# can-hat.net
KiCad netlist of a schematic drawn in EAGLE
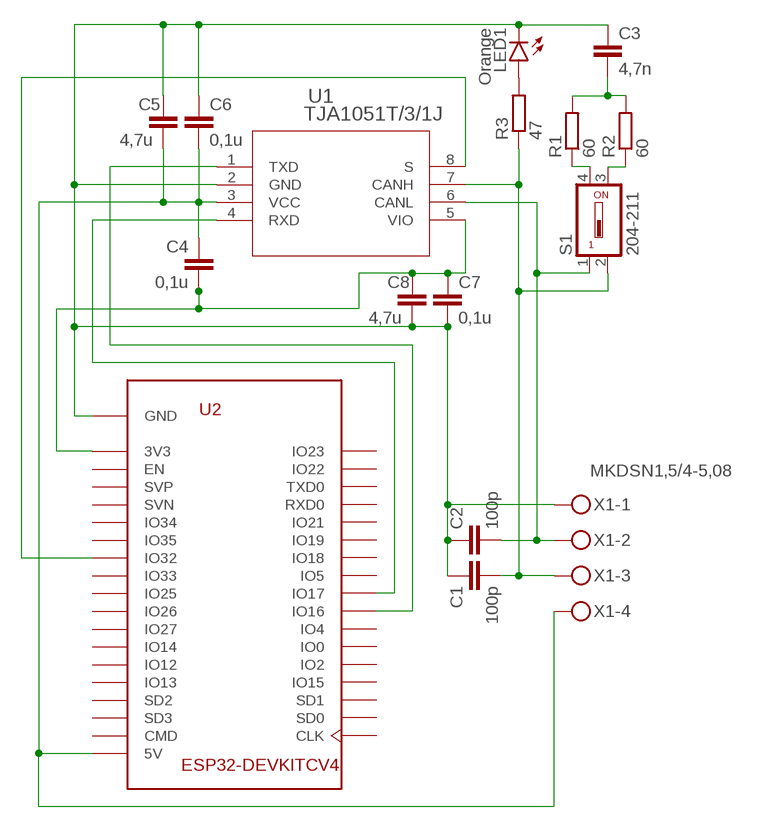
[diagram p0: schematic, sheet 1]

(export (version "E")
  (design (tool "Eeschema 10.0.6"))
  (components
    (comp (ref "C1")
      (value "100p")
      (footprint "eagle-import:C0603")
      (libsource (lib "eagle-import") (part "C-EUC0603"))
    )
    (comp (ref "C2")
      (value "100p")
      (footprint "eagle-import:C0603")
      (libsource (lib "eagle-import") (part "C-EUC0603"))
    )
    (comp (ref "C3")
      (value "4,7n")
      (footprint "eagle-import:C0603")
      (libsource (lib "eagle-import") (part "C-EUC0603"))
    )
    (comp (ref "C4")
      (value "0,1u")
      (footprint "eagle-import:C0603")
      (libsource (lib "eagle-import") (part "C-EUC0603"))
    )
    (comp (ref "C5")
      (value "4,7u")
      (footprint "eagle-import:C0603")
      (libsource (lib "eagle-import") (part "C-EUC0603"))
    )
    (comp (ref "C6")
      (value "0,1u")
      (footprint "eagle-import:C0603")
      (libsource (lib "eagle-import") (part "C-EUC0603"))
    )
    (comp (ref "C7")
      (value "0,1u")
      (footprint "eagle-import:C0603")
      (libsource (lib "eagle-import") (part "C-EUC0603"))
    )
    (comp (ref "C8")
      (value "4,7u")
      (footprint "eagle-import:C0603")
      (libsource (lib "eagle-import") (part "C-EUC0603"))
    )
    (comp (ref "LED1")
      (value "Orange")
      (footprint "eagle-import:CHIP-LED0603")
      (libsource (lib "eagle-import") (part "LEDCHIP-LED0603"))
    )
    (comp (ref "R1")
      (value "60")
      (footprint "eagle-import:R0603")
      (libsource (lib "eagle-import") (part "R-EU_R0603"))
    )
    (comp (ref "R2")
      (value "60")
      (footprint "eagle-import:R0603")
      (libsource (lib "eagle-import") (part "R-EU_R0603"))
    )
    (comp (ref "R3")
      (value "47")
      (footprint "eagle-import:R0603")
      (libsource (lib "eagle-import") (part "R-EU_R0603"))
    )
    (comp (ref "S1")
      (value "204-211")
      (footprint "eagle-import:204-211ST")
      (libsource (lib "eagle-import") (part "204-211"))
    )
    (comp (ref "U1")
      (value "TJA1051T/3/1J")
      (footprint "eagle-import:SO8_SOT96-1_NXP")
      (fields (field (name "COPYRIGHT") "Copyright (C) 2018 Accelerated Designs. All rights reserved"))
      (libsource (lib "eagle-import") (part "TJA1051T/3/1J"))
    )
    (comp (ref "U2")
      (value "ESP32-DEVKITCV4")
      (footprint "eagle-import:DEVKIT-C")
      (libsource (lib "eagle-import") (part "ESP32-DEVKITCV4"))
    )
    (comp (ref "X1")
      (value "MKDSN1,5/4-5,08")
      (footprint "eagle-import:MKDSN1,5_4-5,08")
      (libsource (lib "eagle-import") (part "MKDSN1,5/4-5,08"))
    )
  )
  (nets
    (net (code "1") (name "Net-(C3-Pad2)") (class "Default")
      (node (ref "C3") (pin "2") (pinfunction "2_2") (pintype "passive"))
      (node (ref "R1") (pin "2") (pinfunction "2_2") (pintype "passive"))
      (node (ref "R2") (pin "2") (pinfunction "2_2") (pintype "passive"))
    )
    (net (code "2") (name "Net-(LED1-PadA)") (class "Default")
      (node (ref "LED1") (pin "A") (pinfunction "A_A") (pintype "passive"))
      (node (ref "R3") (pin "2") (pinfunction "2_2") (pintype "passive"))
    )
    (net (code "3") (name "Net-(R1-Pad1)") (class "Default")
      (node (ref "R1") (pin "1") (pinfunction "1_1") (pintype "passive"))
      (node (ref "S1") (pin "4") (pinfunction "4_4") (pintype "passive"))
    )
    (net (code "4") (name "Net-(R2-Pad1)") (class "Default")
      (node (ref "R2") (pin "1") (pinfunction "1_1") (pintype "passive"))
      (node (ref "S1") (pin "3") (pinfunction "3_3") (pintype "passive"))
    )
    (net (code "5") (name "Net-(U1-CANH)") (class "Default")
      (node (ref "C1") (pin "1") (pinfunction "1_1") (pintype "passive"))
      (node (ref "R3") (pin "1") (pinfunction "1_1") (pintype "passive"))
      (node (ref "S1") (pin "2") (pinfunction "2_2") (pintype "passive"))
      (node (ref "U1") (pin "7") (pinfunction "CANH_7") (pintype "bidirectional"))
      (node (ref "X1") (pin "3") (pinfunction "KL_3") (pintype "passive"))
    )
    (net (code "6") (name "Net-(U1-CANL)") (class "Default")
      (node (ref "C2") (pin "2") (pinfunction "2_2") (pintype "passive"))
      (node (ref "S1") (pin "1") (pinfunction "1_1") (pintype "passive"))
      (node (ref "U1") (pin "6") (pinfunction "CANL_6") (pintype "bidirectional"))
      (node (ref "X1") (pin "2") (pinfunction "KL_2") (pintype "passive"))
    )
    (net (code "7") (name "Net-(U1-GND)") (class "Default")
      (node (ref "C1") (pin "2") (pinfunction "2_2") (pintype "passive"))
      (node (ref "C2") (pin "1") (pinfunction "1_1") (pintype "passive"))
      (node (ref "C3") (pin "1") (pinfunction "1_1") (pintype "passive"))
      (node (ref "C5") (pin "1") (pinfunction "1_1") (pintype "passive"))
      (node (ref "C6") (pin "1") (pinfunction "1_1") (pintype "passive"))
      (node (ref "C7") (pin "2") (pinfunction "2_2") (pintype "passive"))
      (node (ref "C8") (pin "2") (pinfunction "2_2") (pintype "passive"))
      (node (ref "LED1") (pin "C") (pinfunction "C_C") (pintype "passive"))
      (node (ref "U1") (pin "2") (pinfunction "GND_2") (pintype "passive"))
      (node (ref "U2") (pin "GND1") (pinfunction "GND_GND1") (pintype "power_in"))
      (node (ref "U2") (pin "GND2") (pinfunction "GND_GND2") (pintype "power_in"))
      (node (ref "U2") (pin "GND3") (pinfunction "GND_GND3") (pintype "power_in"))
      (node (ref "X1") (pin "1") (pinfunction "KL_1") (pintype "passive"))
    )
    (net (code "8") (name "Net-(U1-RXD)") (class "Default")
      (node (ref "U1") (pin "4") (pinfunction "RXD_4") (pintype "output"))
      (node (ref "U2") (pin "IO17") (pinfunction "IO17_IO17") (pintype "bidirectional"))
    )
    (net (code "9") (name "Net-(U1-S)") (class "Default")
      (node (ref "U1") (pin "8") (pinfunction "S_8") (pintype "input"))
      (node (ref "U2") (pin "IO32") (pinfunction "IO32_IO32") (pintype "bidirectional"))
    )
    (net (code "10") (name "Net-(U1-TXD)") (class "Default")
      (node (ref "U1") (pin "1") (pinfunction "TXD_1") (pintype "input"))
      (node (ref "U2") (pin "IO16") (pinfunction "IO16_IO16") (pintype "bidirectional"))
    )
    (net (code "11") (name "Net-(U1-VCC)") (class "Default")
      (node (ref "C4") (pin "1") (pinfunction "1_1") (pintype "passive"))
      (node (ref "C5") (pin "2") (pinfunction "2_2") (pintype "passive"))
      (node (ref "C6") (pin "2") (pinfunction "2_2") (pintype "passive"))
      (node (ref "U1") (pin "3") (pinfunction "VCC_3") (pintype "power_in"))
      (node (ref "U2") (pin "5V") (pinfunction "5V_5V") (pintype "power_in"))
      (node (ref "X1") (pin "4") (pinfunction "KL_4") (pintype "passive"))
    )
    (net (code "12") (name "Net-(U1-VIO)") (class "Default")
      (node (ref "C4") (pin "2") (pinfunction "2_2") (pintype "passive"))
      (node (ref "C7") (pin "1") (pinfunction "1_1") (pintype "passive"))
      (node (ref "C8") (pin "1") (pinfunction "1_1") (pintype "passive"))
      (node (ref "U1") (pin "5") (pinfunction "VIO_5") (pintype "power_in"))
      (node (ref "U2") (pin "3V3") (pinfunction "3V3_3V3") (pintype "power_in"))
    )
    (net (code "13") (name "unconnected-(U2-PadCLK)") (class "Default")
      (node (ref "U2") (pin "CLK") (pinfunction "CLK_CLK") (pintype "bidirectional"))
    )
    (net (code "14") (name "unconnected-(U2-PadCMD)") (class "Default")
      (node (ref "U2") (pin "CMD") (pinfunction "CMD_CMD") (pintype "bidirectional"))
    )
    (net (code "15") (name "unconnected-(U2-PadEN)") (class "Default")
      (node (ref "U2") (pin "EN") (pinfunction "EN_EN") (pintype "bidirectional"))
    )
    (net (code "16") (name "unconnected-(U2-PadIO0)") (class "Default")
      (node (ref "U2") (pin "IO0") (pinfunction "IO0_IO0") (pintype "bidirectional"))
    )
    (net (code "17") (name "unconnected-(U2-PadIO2)") (class "Default")
      (node (ref "U2") (pin "IO2") (pinfunction "IO2_IO2") (pintype "bidirectional"))
    )
    (net (code "18") (name "unconnected-(U2-PadIO4)") (class "Default")
      (node (ref "U2") (pin "IO4") (pinfunction "IO4_IO4") (pintype "bidirectional"))
    )
    (net (code "19") (name "unconnected-(U2-PadIO5)") (class "Default")
      (node (ref "U2") (pin "IO5") (pinfunction "IO5_IO5") (pintype "bidirectional"))
    )
    (net (code "20") (name "unconnected-(U2-PadIO12)") (class "Default")
      (node (ref "U2") (pin "IO12") (pinfunction "IO12_IO12") (pintype "bidirectional"))
    )
    (net (code "21") (name "unconnected-(U2-PadIO13)") (class "Default")
      (node (ref "U2") (pin "IO13") (pinfunction "IO13_IO13") (pintype "bidirectional"))
    )
    (net (code "22") (name "unconnected-(U2-PadIO14)") (class "Default")
      (node (ref "U2") (pin "IO14") (pinfunction "IO14_IO14") (pintype "bidirectional"))
    )
    (net (code "23") (name "unconnected-(U2-PadIO15)") (class "Default")
      (node (ref "U2") (pin "IO15") (pinfunction "IO15_IO15") (pintype "bidirectional"))
    )
    (net (code "24") (name "unconnected-(U2-PadIO18)") (class "Default")
      (node (ref "U2") (pin "IO18") (pinfunction "IO18_IO18") (pintype "bidirectional"))
    )
    (net (code "25") (name "unconnected-(U2-PadIO19)") (class "Default")
      (node (ref "U2") (pin "IO19") (pinfunction "IO19_IO19") (pintype "bidirectional"))
    )
    (net (code "26") (name "unconnected-(U2-PadIO21)") (class "Default")
      (node (ref "U2") (pin "IO21") (pinfunction "IO21_IO21") (pintype "bidirectional"))
    )
    (net (code "27") (name "unconnected-(U2-PadIO22)") (class "Default")
      (node (ref "U2") (pin "IO22") (pinfunction "IO22_IO22") (pintype "bidirectional"))
    )
    (net (code "28") (name "unconnected-(U2-PadIO23)") (class "Default")
      (node (ref "U2") (pin "IO23") (pinfunction "IO23_IO23") (pintype "bidirectional"))
    )
    (net (code "29") (name "unconnected-(U2-PadIO25)") (class "Default")
      (node (ref "U2") (pin "IO25") (pinfunction "IO25_IO25") (pintype "bidirectional"))
    )
    (net (code "30") (name "unconnected-(U2-PadIO26)") (class "Default")
      (node (ref "U2") (pin "IO26") (pinfunction "IO26_IO26") (pintype "bidirectional"))
    )
    (net (code "31") (name "unconnected-(U2-PadIO27)") (class "Default")
      (node (ref "U2") (pin "IO27") (pinfunction "IO27_IO27") (pintype "bidirectional"))
    )
    (net (code "32") (name "unconnected-(U2-PadIO33)") (class "Default")
      (node (ref "U2") (pin "IO33") (pinfunction "IO33_IO33") (pintype "bidirectional"))
    )
    (net (code "33") (name "unconnected-(U2-PadIO34)") (class "Default")
      (node (ref "U2") (pin "IO34") (pinfunction "IO34_IO34") (pintype "bidirectional"))
    )
    (net (code "34") (name "unconnected-(U2-PadIO35)") (class "Default")
      (node (ref "U2") (pin "IO35") (pinfunction "IO35_IO35") (pintype "bidirectional"))
    )
    (net (code "35") (name "unconnected-(U2-PadRXD0)") (class "Default")
      (node (ref "U2") (pin "RXD0") (pinfunction "RXD0_RXD0") (pintype "bidirectional"))
    )
    (net (code "36") (name "unconnected-(U2-PadSD0)") (class "Default")
      (node (ref "U2") (pin "SD0") (pinfunction "SD0_SD0") (pintype "bidirectional"))
    )
    (net (code "37") (name "unconnected-(U2-PadSD1)") (class "Default")
      (node (ref "U2") (pin "SD1") (pinfunction "SD1_SD1") (pintype "bidirectional"))
    )
    (net (code "38") (name "unconnected-(U2-PadSD2)") (class "Default")
      (node (ref "U2") (pin "SD2") (pinfunction "SD2_SD2") (pintype "bidirectional"))
    )
    (net (code "39") (name "unconnected-(U2-PadSD3)") (class "Default")
      (node (ref "U2") (pin "SD3") (pinfunction "SD3_SD3") (pintype "bidirectional"))
    )
    (net (code "40") (name "unconnected-(U2-PadSVN)") (class "Default")
      (node (ref "U2") (pin "SVN") (pinfunction "SVN_SVN") (pintype "bidirectional"))
    )
    (net (code "41") (name "unconnected-(U2-PadSVP)") (class "Default")
      (node (ref "U2") (pin "SVP") (pinfunction "SVP_SVP") (pintype "bidirectional"))
    )
    (net (code "42") (name "unconnected-(U2-PadTXD0)") (class "Default")
      (node (ref "U2") (pin "TXD0") (pinfunction "TXD0_TXD0") (pintype "bidirectional"))
    )
  )
)
